# 3_Communication.net
KiCad netlist of a schematic drawn in Altium Designer
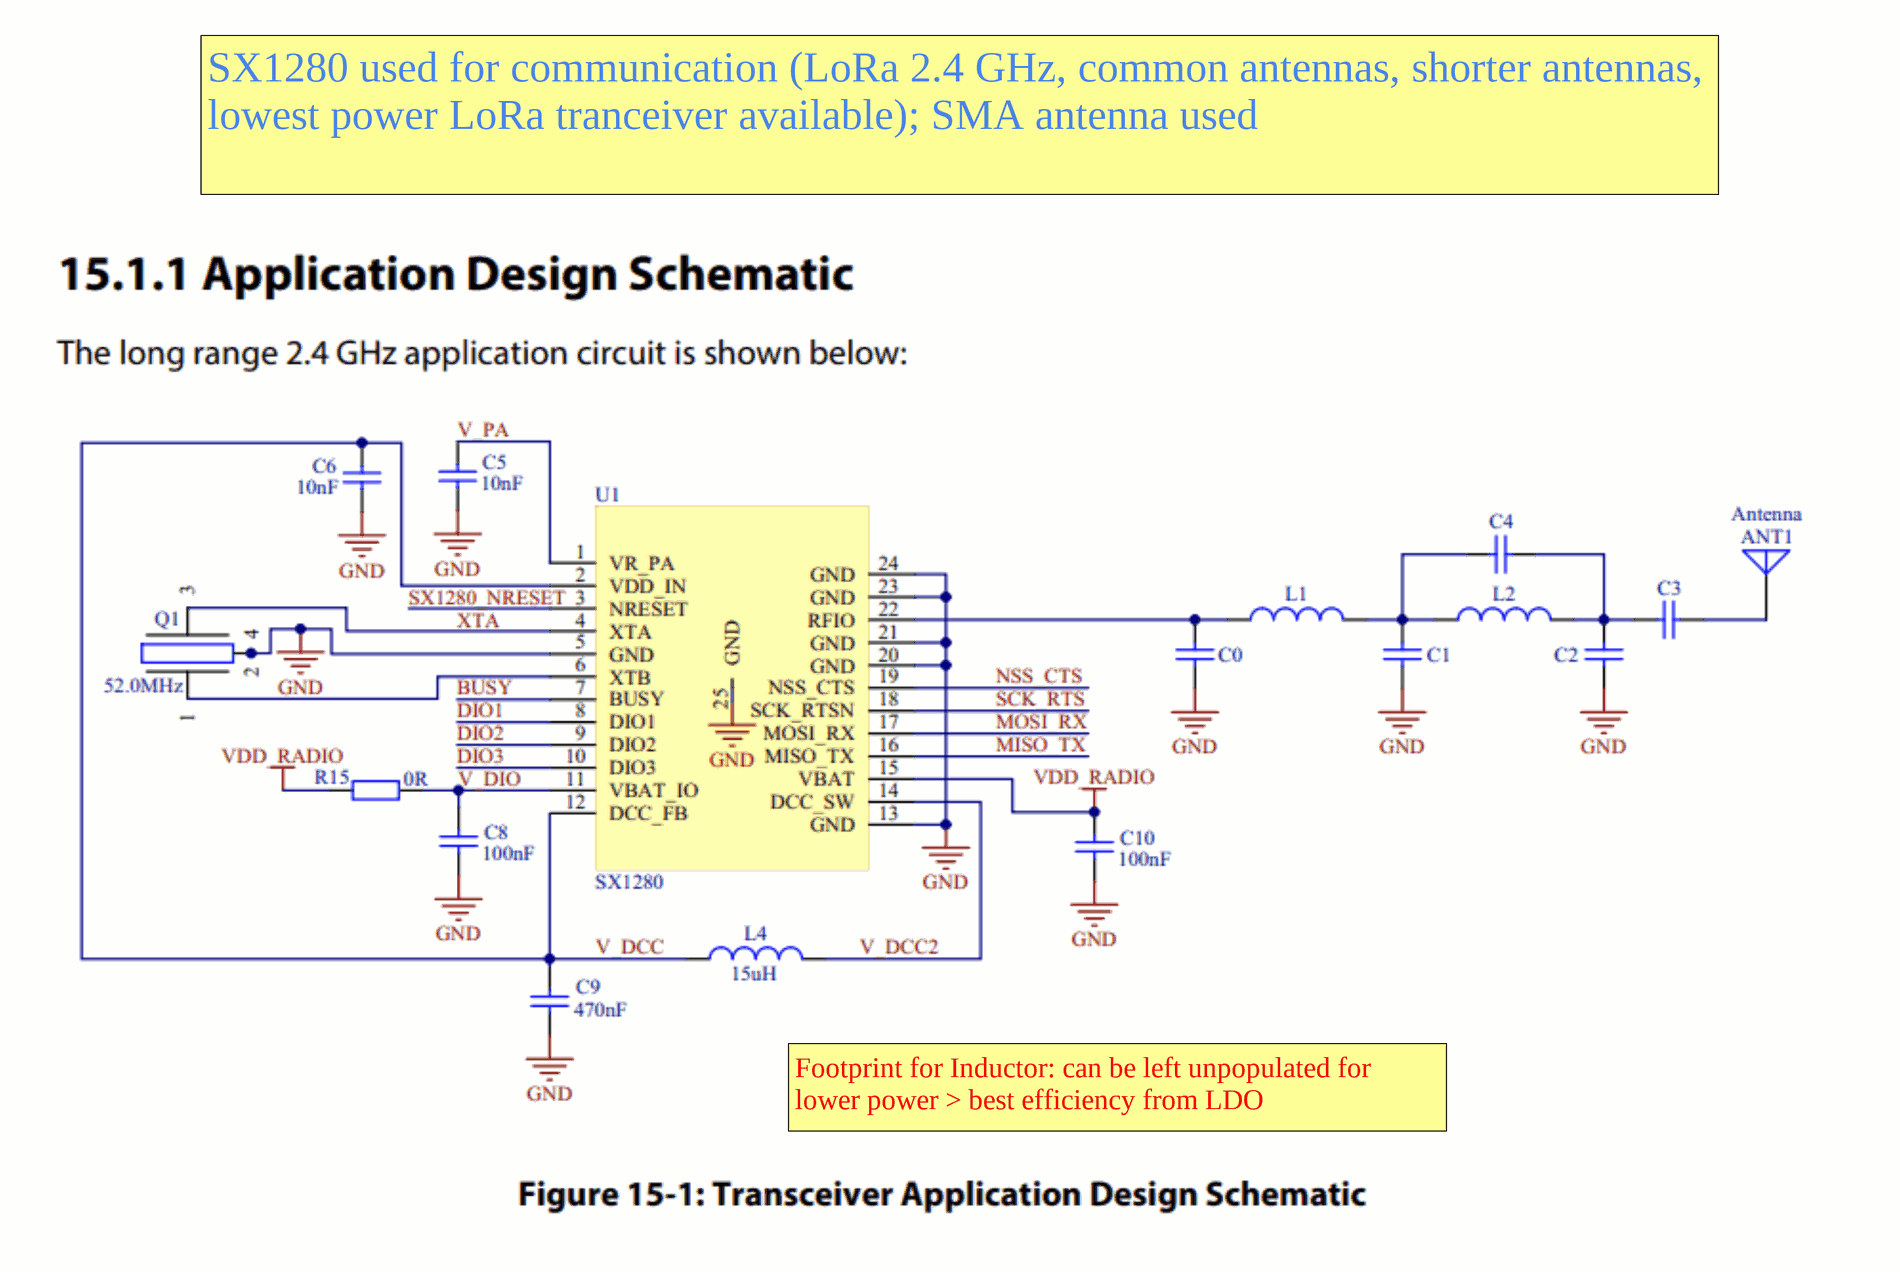
[diagram p0: 3_Communication.SchDoc, left]
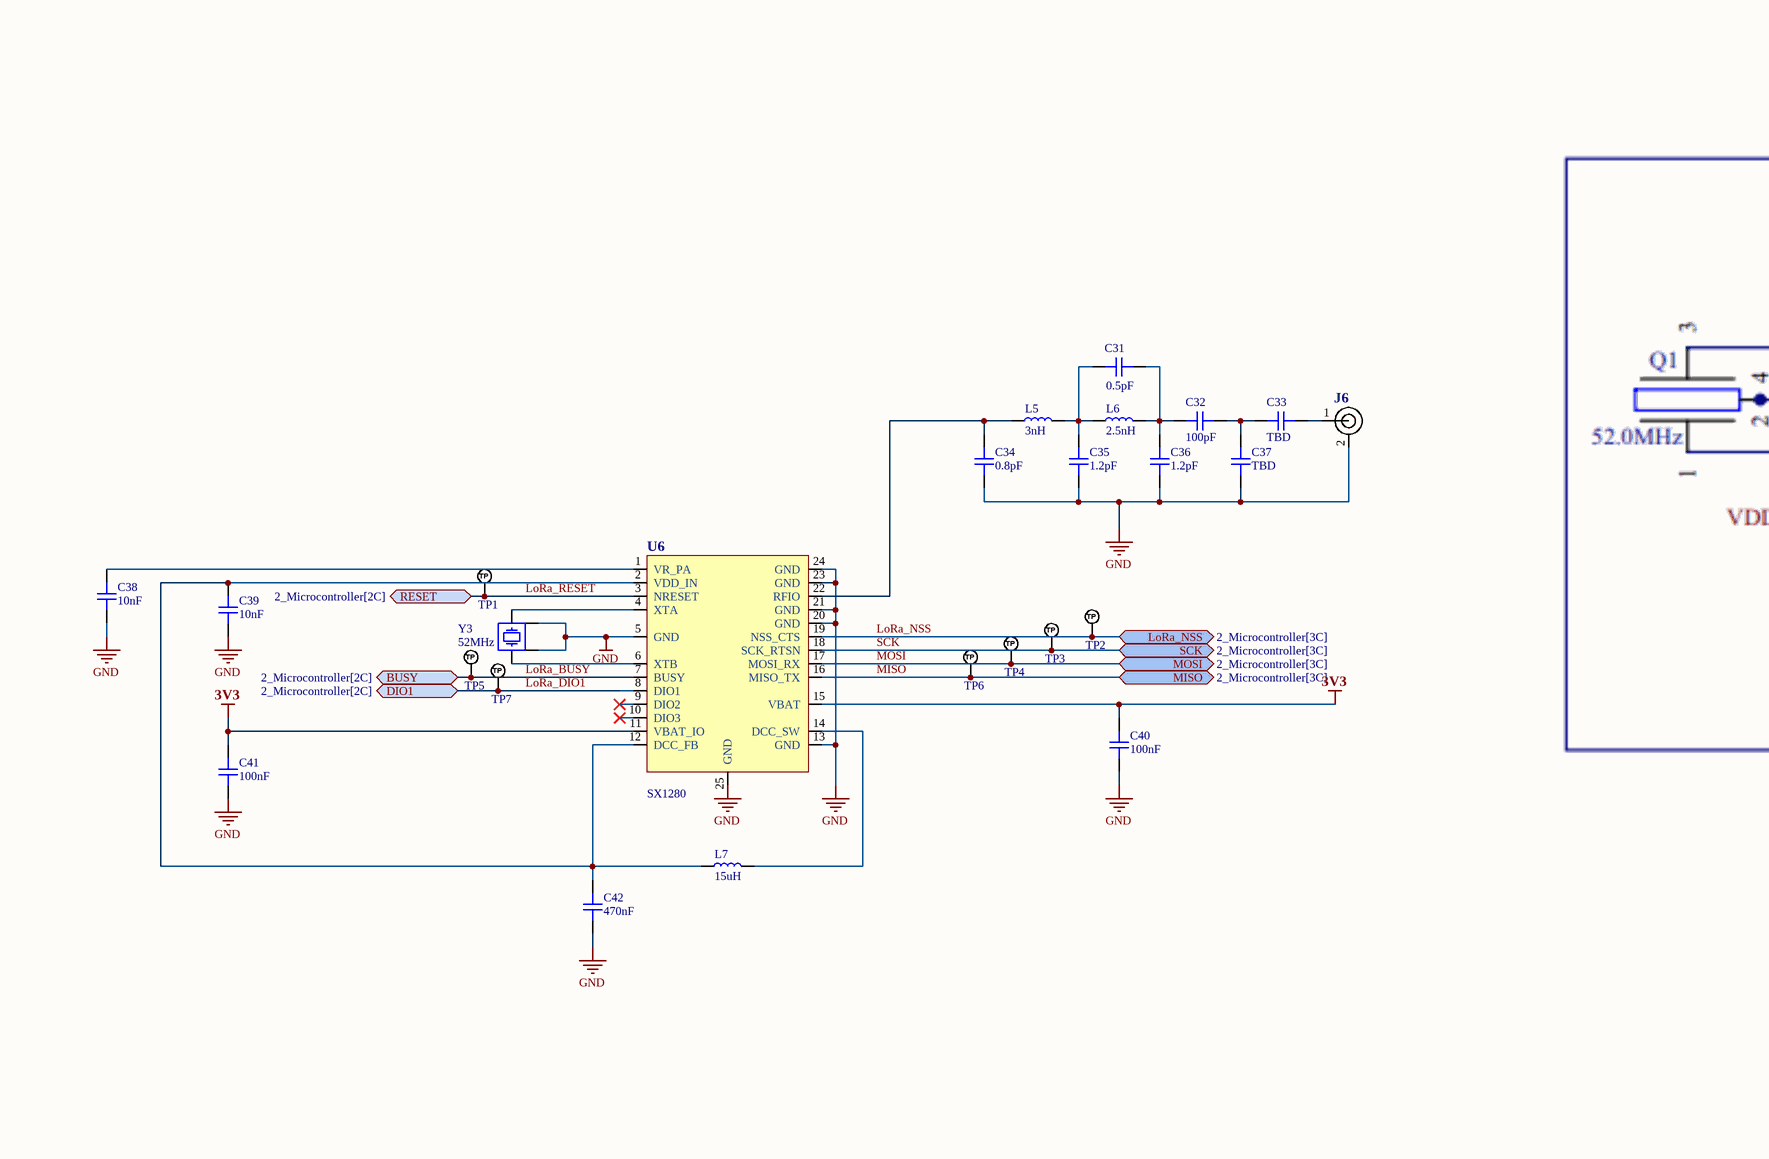
[diagram p1: 3_Communication.SchDoc, middle]
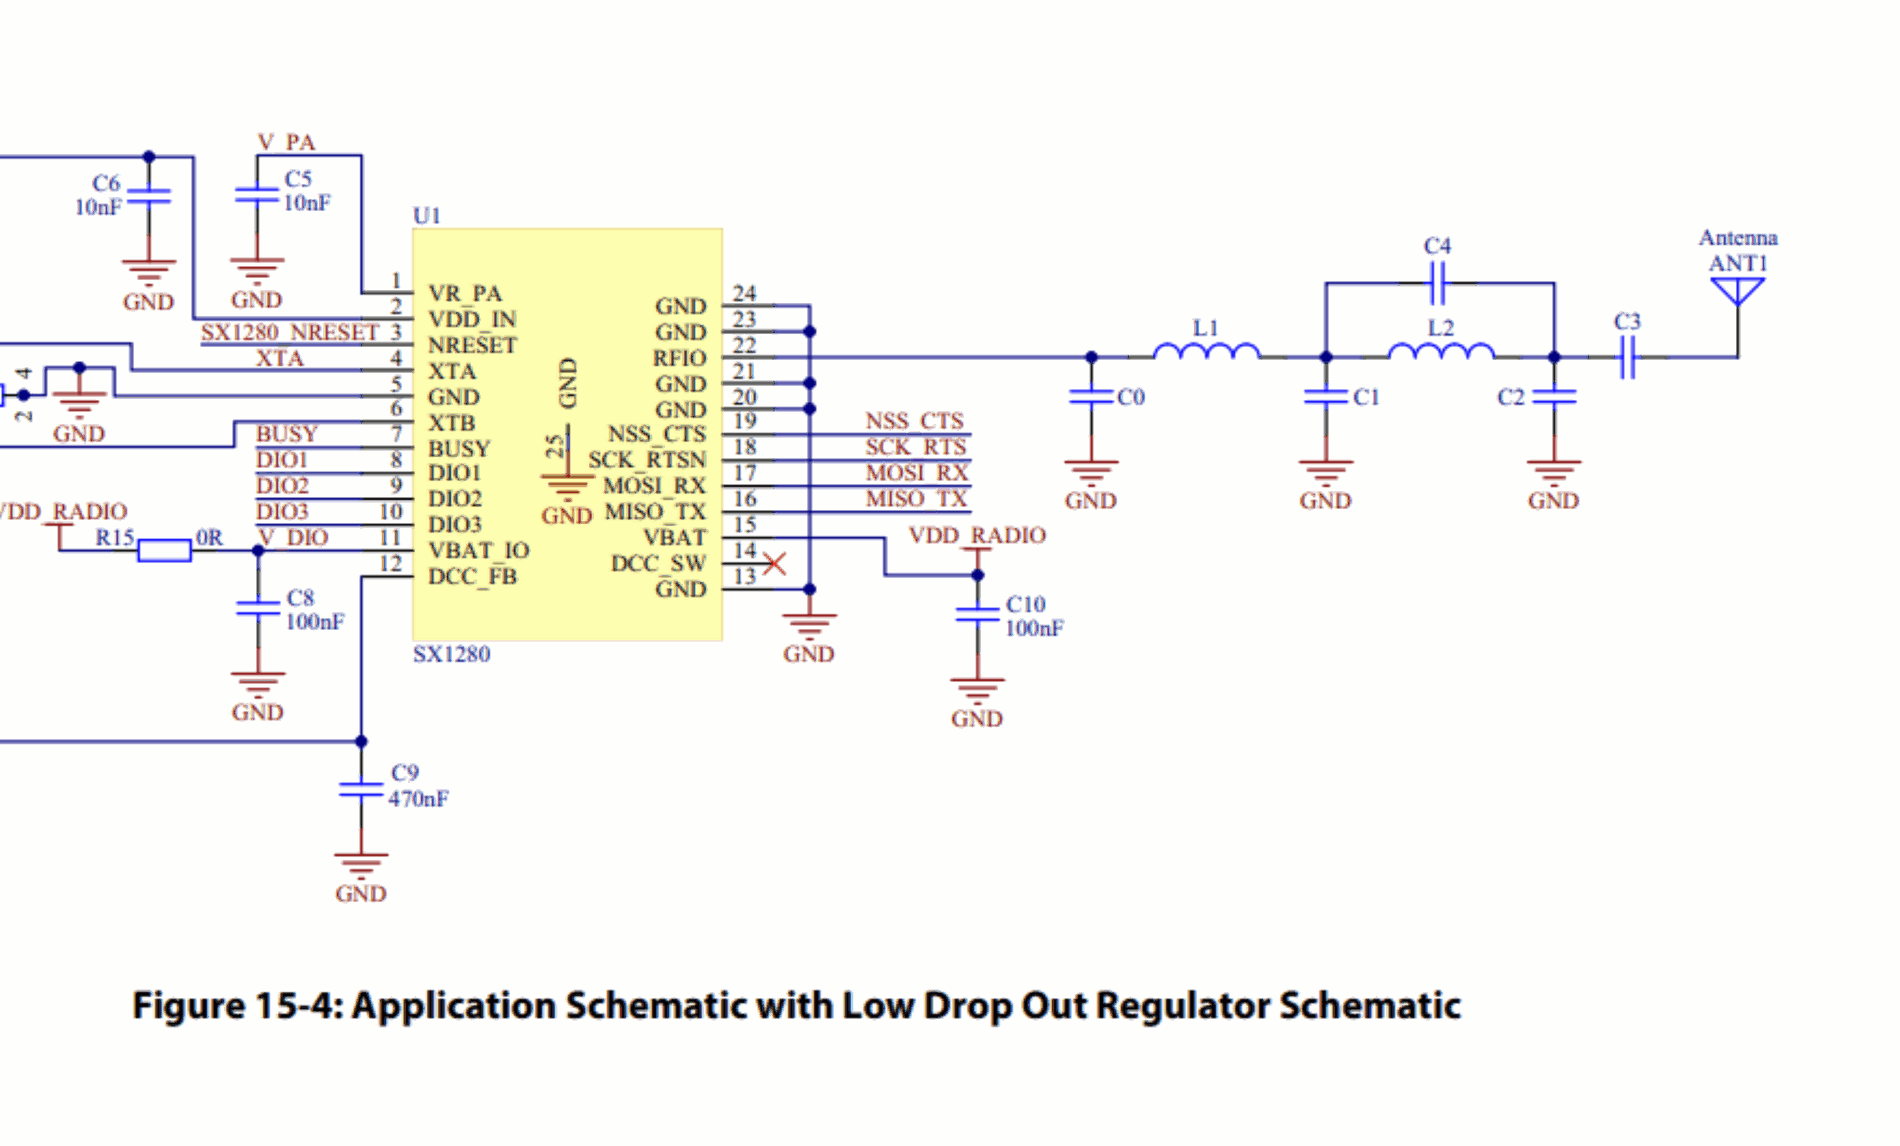
[diagram p2: 3_Communication.SchDoc, right]

(export (version "E")
  (design (tool "Eeschema 10.0.6"))
  (components
    (comp (ref "C31")
      (value "0.5pF")
      (footprint "C0603")
      (description "Capacitor SMD 0603")
      (libsource (lib "Schlib_H2") (part "CAP_0603"))
    )
    (comp (ref "C32")
      (value "100pF")
      (footprint "C0603")
      (description "Capacitor SMD 0603")
      (libsource (lib "Schlib_H2") (part "CAP_0603"))
    )
    (comp (ref "C33")
      (value "TBD")
      (footprint "C0805")
      (description "Capacitor SMD 0805")
      (libsource (lib "Schlib_H2") (part "CAP_0603"))
    )
    (comp (ref "C34")
      (value "0.8pF")
      (footprint "C0603")
      (description "Capacitor SMD 0805")
      (libsource (lib "Schlib_H2") (part "CAP_0805"))
    )
    (comp (ref "C35")
      (value "1.2pF")
      (footprint "C0603")
      (description "Capacitor SMD 0603")
      (libsource (lib "Schlib_H2") (part "CAP_0603"))
    )
    (comp (ref "C36")
      (value "1.2pF")
      (footprint "C0603")
      (description "Capacitor SMD 0603")
      (libsource (lib "Schlib_H2") (part "CAP_0603"))
    )
    (comp (ref "C37")
      (value "TBD")
      (footprint "C0805")
      (description "Capacitor SMD 0805")
      (libsource (lib "Schlib_H2") (part "CAP_0603"))
    )
    (comp (ref "C38")
      (value "10nF")
      (footprint "C0603")
      (description "Capacitor SMD 0603")
      (libsource (lib "Schlib_H2") (part "CAP_0603"))
    )
    (comp (ref "C39")
      (value "10nF")
      (footprint "C0603")
      (description "Capacitor SMD 0603")
      (libsource (lib "Schlib_H2") (part "CAP_0603"))
    )
    (comp (ref "C40")
      (value "100nF")
      (footprint "C0603")
      (description "Capacitor SMD 0603")
      (libsource (lib "Schlib_H2") (part "CAP_0603"))
    )
    (comp (ref "C41")
      (value "100nF")
      (footprint "C0603")
      (description "Capacitor SMD 0603")
      (libsource (lib "Schlib_H2") (part "CAP_0603"))
    )
    (comp (ref "C42")
      (value "470nF")
      (footprint "C0603")
      (description "Capacitor SMD 0603")
      (libsource (lib "Schlib_H2") (part "CAP_0603"))
    )
    (comp (ref "J6")
      (value "SMA_EDGE_CONN")
      (footprint "CON_SMA-EDGE-S")
      (description "RF Connector SMA Female 50 Ohms 18 GHz PCB Edge Mount")
      (fields
        (field (name "MANUFACTURER") "RF Solutions")
        (field (name "MANUFACTURER PART NUMBER") "CON-SMA-EDGE-S")
      )
      (libsource (lib "Schlib_H2") (part "CON-SMA-EDGE-S"))
    )
    (comp (ref "L5")
      (value "3nH")
      (footprint "L0603")
      (description "Inductor SMD 0603")
      (libsource (lib "Schlib_H2") (part "IND_0603"))
    )
    (comp (ref "L6")
      (value "2.5nH")
      (footprint "L0603")
      (description "Inductor SMD 0603")
      (libsource (lib "Schlib_H2") (part "IND_0603"))
    )
    (comp (ref "L7")
      (value "15uH")
      (footprint "IND_3.2_4")
      (description "Inductor SMD 0603")
      (libsource (lib "Schlib_H2") (part "IND_0603"))
    )
    (comp (ref "TP1")
      (value "TP_NOBOM")
      (footprint "TEST_PAD_THD")
      (description "Test Point Round 1mm (NO BOM)")
      (libsource (lib "Schlib_H2") (part "TEST_POINT_RND_1MM"))
    )
    (comp (ref "TP2")
      (value "TP_NOBOM")
      (footprint "TEST_PAD_THD")
      (description "Test Point Round 1mm (NO BOM)")
      (libsource (lib "Schlib_H2") (part "TEST_POINT_RND_1MM"))
    )
    (comp (ref "TP3")
      (value "TP_NOBOM")
      (footprint "TEST_PAD_THD")
      (description "Test Point Round 1mm (NO BOM)")
      (libsource (lib "Schlib_H2") (part "TEST_POINT_RND_1MM"))
    )
    (comp (ref "TP4")
      (value "TP_NOBOM")
      (footprint "TEST_PAD_THD")
      (description "Test Point Round 1mm (NO BOM)")
      (libsource (lib "Schlib_H2") (part "TEST_POINT_RND_1MM"))
    )
    (comp (ref "TP5")
      (value "TP_NOBOM")
      (footprint "TEST_PAD_THD")
      (description "Test Point Round 1mm (NO BOM)")
      (libsource (lib "Schlib_H2") (part "TEST_POINT_RND_1MM"))
    )
    (comp (ref "TP6")
      (value "TP_NOBOM")
      (footprint "TEST_PAD_THD")
      (description "Test Point Round 1mm (NO BOM)")
      (libsource (lib "Schlib_H2") (part "TEST_POINT_RND_1MM"))
    )
    (comp (ref "TP7")
      (value "TP_NOBOM")
      (footprint "TEST_PAD_THD")
      (description "Test Point Round 1mm (NO BOM)")
      (libsource (lib "Schlib_H2") (part "TEST_POINT_RND_1MM"))
    )
    (comp (ref "U6")
      (value "SX1280")
      (footprint "QFN-24_4x4_0.5")
      (description "Low power LoRa transceiver operating at 2.4GHz with ranging capability")
      (libsource (lib "Schlib_H2") (part "SX1280"))
    )
    (comp (ref "Y3")
      (value "52MHz")
      (footprint "CRYSTAL_2016_4P")
      (description "Crystal")
      (fields
        (field (name "MANUFACTURER") "Epson")
        (field (name "MANUFACTURER PART NUMBER") "TSX-3225 24.0000MF15X-AC")
      )
      (libsource (lib "Schlib_H2") (part "Crystal"))
    )
  )
  (nets
    (net (code "1") (name "/LoRa_BUSY") (class "Default")
      (node (ref "TP5") (pin "1") (pinfunction "TP_1") (pintype "passive"))
      (node (ref "U6") (pin "7") (pinfunction "BUSY_7") (pintype "passive"))
    )
    (net (code "2") (name "/LoRa_DIO1") (class "Default")
      (node (ref "TP7") (pin "1") (pinfunction "TP_1") (pintype "passive"))
      (node (ref "U6") (pin "8") (pinfunction "DIO1_8") (pintype "passive"))
    )
    (net (code "3") (name "/LoRa_NSS") (class "Default")
      (node (ref "TP2") (pin "1") (pinfunction "TP_1") (pintype "passive"))
      (node (ref "U6") (pin "19") (pinfunction "NSS_CTS_19") (pintype "passive"))
    )
    (net (code "4") (name "/LoRa_RESET") (class "Default")
      (node (ref "TP1") (pin "1") (pinfunction "TP_1") (pintype "passive"))
      (node (ref "U6") (pin "3") (pinfunction "NRESET_3") (pintype "passive"))
    )
    (net (code "5") (name "/MISO") (class "Default")
      (node (ref "TP6") (pin "1") (pinfunction "TP_1") (pintype "passive"))
      (node (ref "U6") (pin "16") (pinfunction "MISO_TX_16") (pintype "passive"))
    )
    (net (code "6") (name "/MOSI") (class "Default")
      (node (ref "TP4") (pin "1") (pinfunction "TP_1") (pintype "passive"))
      (node (ref "U6") (pin "17") (pinfunction "MOSI_RX_17") (pintype "passive"))
    )
    (net (code "7") (name "/SCK") (class "Default")
      (node (ref "TP3") (pin "1") (pinfunction "TP_1") (pintype "passive"))
      (node (ref "U6") (pin "18") (pinfunction "SCK_RTSN_18") (pintype "passive"))
    )
    (net (code "8") (name "3V3") (class "Default")
      (node (ref "C40") (pin "2") (pinfunction "2_2") (pintype "passive"))
      (node (ref "C41") (pin "2") (pinfunction "2_2") (pintype "passive"))
      (node (ref "U6") (pin "11") (pinfunction "VBAT_IO_11") (pintype "passive"))
      (node (ref "U6") (pin "15") (pinfunction "VBAT_15") (pintype "passive"))
    )
    (net (code "9") (name "GND") (class "Default")
      (node (ref "C34") (pin "1") (pinfunction "1_1") (pintype "passive"))
      (node (ref "C35") (pin "1") (pinfunction "1_1") (pintype "passive"))
      (node (ref "C36") (pin "1") (pinfunction "1_1") (pintype "passive"))
      (node (ref "C37") (pin "1") (pinfunction "1_1") (pintype "passive"))
      (node (ref "C38") (pin "1") (pinfunction "1_1") (pintype "passive"))
      (node (ref "C39") (pin "1") (pinfunction "1_1") (pintype "passive"))
      (node (ref "C40") (pin "1") (pinfunction "1_1") (pintype "passive"))
      (node (ref "C41") (pin "1") (pinfunction "1_1") (pintype "passive"))
      (node (ref "C42") (pin "1") (pinfunction "1_1") (pintype "passive"))
      (node (ref "J6") (pin "2") (pinfunction "2_2") (pintype "passive"))
      (node (ref "U6") (pin "13") (pinfunction "GND_13") (pintype "passive"))
      (node (ref "U6") (pin "20") (pinfunction "GND_20") (pintype "passive"))
      (node (ref "U6") (pin "21") (pinfunction "GND_21") (pintype "passive"))
      (node (ref "U6") (pin "23") (pinfunction "GND_23") (pintype "passive"))
      (node (ref "U6") (pin "24") (pinfunction "GND_24") (pintype "passive"))
      (node (ref "U6") (pin "25") (pinfunction "GND_25") (pintype "passive"))
      (node (ref "U6") (pin "5") (pinfunction "GND_5") (pintype "passive"))
      (node (ref "Y3") (pin "2") (pinfunction "2_2") (pintype "passive"))
      (node (ref "Y3") (pin "4") (pinfunction "4_4") (pintype "passive"))
    )
    (net (code "10") (name "Net-(C31-Pad1)") (class "Default")
      (node (ref "C31") (pin "1") (pinfunction "1_1") (pintype "passive"))
      (node (ref "C32") (pin "2") (pinfunction "2_2") (pintype "passive"))
      (node (ref "C36") (pin "2") (pinfunction "2_2") (pintype "passive"))
      (node (ref "L6") (pin "2") (pinfunction "2_2") (pintype "passive"))
    )
    (net (code "11") (name "Net-(C31-Pad2)") (class "Default")
      (node (ref "C31") (pin "2") (pinfunction "2_2") (pintype "passive"))
      (node (ref "C35") (pin "2") (pinfunction "2_2") (pintype "passive"))
      (node (ref "L5") (pin "2") (pinfunction "2_2") (pintype "passive"))
      (node (ref "L6") (pin "1") (pinfunction "1_1") (pintype "passive"))
    )
    (net (code "12") (name "Net-(C32-Pad1)") (class "Default")
      (node (ref "C32") (pin "1") (pinfunction "1_1") (pintype "passive"))
      (node (ref "C33") (pin "2") (pinfunction "2_2") (pintype "passive"))
      (node (ref "C37") (pin "2") (pinfunction "2_2") (pintype "passive"))
    )
    (net (code "13") (name "Net-(C33-Pad1)") (class "Default")
      (node (ref "C33") (pin "1") (pinfunction "1_1") (pintype "passive"))
      (node (ref "J6") (pin "1") (pinfunction "1_1") (pintype "passive"))
    )
    (net (code "14") (name "Net-(U6-DCC_FB)") (class "Default")
      (node (ref "C39") (pin "2") (pinfunction "2_2") (pintype "passive"))
      (node (ref "C42") (pin "2") (pinfunction "2_2") (pintype "passive"))
      (node (ref "L7") (pin "1") (pinfunction "1_1") (pintype "passive"))
      (node (ref "U6") (pin "12") (pinfunction "DCC_FB_12") (pintype "passive"))
      (node (ref "U6") (pin "2") (pinfunction "VDD_IN_2") (pintype "passive"))
    )
    (net (code "15") (name "Net-(U6-DCC_SW)") (class "Default")
      (node (ref "L7") (pin "2") (pinfunction "2_2") (pintype "passive"))
      (node (ref "U6") (pin "14") (pinfunction "DCC_SW_14") (pintype "passive"))
    )
    (net (code "16") (name "Net-(U6-RFIO)") (class "Default")
      (node (ref "C34") (pin "2") (pinfunction "2_2") (pintype "passive"))
      (node (ref "L5") (pin "1") (pinfunction "1_1") (pintype "passive"))
      (node (ref "U6") (pin "22") (pinfunction "RFIO_22") (pintype "passive"))
    )
    (net (code "17") (name "Net-(U6-VR_PA)") (class "Default")
      (node (ref "C38") (pin "2") (pinfunction "2_2") (pintype "passive"))
      (node (ref "U6") (pin "1") (pinfunction "VR_PA_1") (pintype "passive"))
    )
    (net (code "18") (name "Net-(U6-XTA)") (class "Default")
      (node (ref "U6") (pin "4") (pinfunction "XTA_4") (pintype "passive"))
      (node (ref "Y3") (pin "3") (pinfunction "3_3") (pintype "passive"))
    )
    (net (code "19") (name "Net-(U6-XTB)") (class "Default")
      (node (ref "U6") (pin "6") (pinfunction "XTB_6") (pintype "passive"))
      (node (ref "Y3") (pin "1") (pinfunction "1_1") (pintype "passive"))
    )
    (net (code "20") (name "unconnected-(U6-DIO2-Pad9)") (class "Default")
      (node (ref "U6") (pin "9") (pinfunction "DIO2_9") (pintype "passive+no_connect"))
    )
    (net (code "21") (name "unconnected-(U6-DIO3-Pad10)") (class "Default")
      (node (ref "U6") (pin "10") (pinfunction "DIO3_10") (pintype "passive+no_connect"))
    )
  )
)
